# Baro_Touch.net
KiCad netlist of a schematic drawn in EAGLE
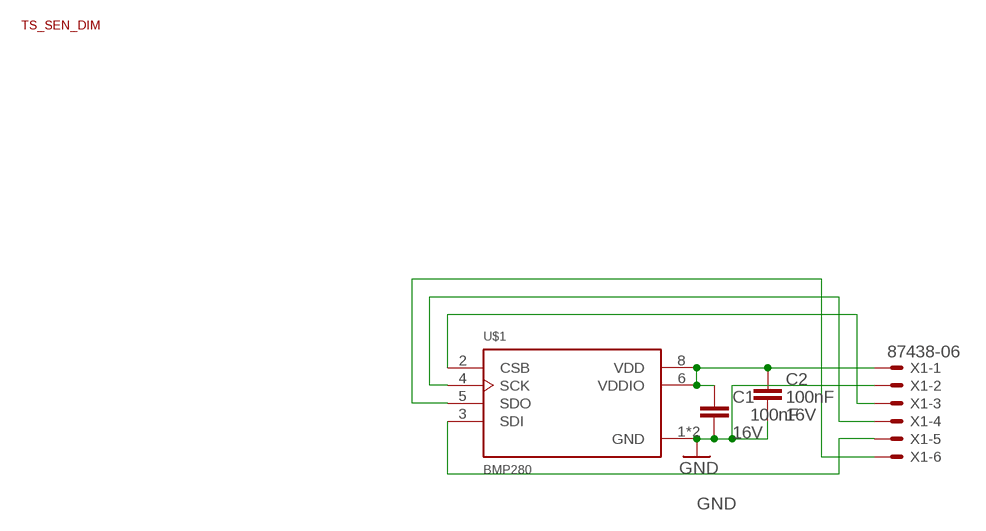
[diagram p0: schematic, sheet 1]

(export (version "E")
  (design (tool "Eeschema 10.0.6"))
  (components
    (comp (ref "C1")
      (value "GCM155R71C104JA55")
      (footprint "eagle-import:C0402")
      (fields
        (field (name "CAPACITANCE") "100nF")
        (field (name "TOLERANCE") "±5%")
        (field (name "VOLTAGE") "16V")
      )
      (libsource (lib "eagle-import") (part "GCM?R71551C104JA55"))
    )
    (comp (ref "C2")
      (value "GCM155R71C104JA55")
      (footprint "eagle-import:C0402")
      (fields
        (field (name "CAPACITANCE") "100nF")
        (field (name "TOLERANCE") "±5%")
        (field (name "VOLTAGE") "16V")
      )
      (libsource (lib "eagle-import") (part "GCM?R71551C104JA55"))
    )
    (comp (ref "DIMENSION1")
      (value "TS_SEN_DIM")
      (footprint "eagle-import:SEN_DIM")
      (libsource (lib "eagle-import") (part "TS_SEN_DIM"))
    )
    (comp (ref "U$1")
      (value "BMP280")
      (footprint "eagle-import:8-SMD")
      (libsource (lib "eagle-import") (part "BMP280"))
    )
    (comp (ref "X1")
      (value "87438-06")
      (footprint "eagle-import:87438-06")
      (fields (field (name "MF") "MOLEX") (field (name "MPN") "87438-0643"))
      (libsource (lib "eagle-import") (part "87438-06"))
    )
  )
  (nets
    (net (code "1") (name "GND") (class "Default")
      (node (ref "C1") (pin "2") (pinfunction "2_2") (pintype "passive"))
      (node (ref "C2") (pin "2") (pinfunction "2_2") (pintype "passive"))
      (node (ref "U$1") (pin "1") (pinfunction "GND_1") (pintype "power_in"))
      (node (ref "U$1") (pin "7") (pinfunction "GND_7") (pintype "power_in"))
      (node (ref "X1") (pin "2") (pinfunction "S_2") (pintype "passive"))
    )
    (net (code "2") (name "Net-(U$1-CSB)") (class "Default")
      (node (ref "U$1") (pin "2") (pinfunction "CSB_2") (pintype "input"))
      (node (ref "X1") (pin "3") (pinfunction "S_3") (pintype "passive"))
    )
    (net (code "3") (name "Net-(U$1-SCK)") (class "Default")
      (node (ref "U$1") (pin "4") (pinfunction "SCK_4") (pintype "input"))
      (node (ref "X1") (pin "4") (pinfunction "S_4") (pintype "passive"))
    )
    (net (code "4") (name "Net-(U$1-SDI)") (class "Default")
      (node (ref "U$1") (pin "3") (pinfunction "SDI_3") (pintype "bidirectional"))
      (node (ref "X1") (pin "5") (pinfunction "S_5") (pintype "passive"))
    )
    (net (code "5") (name "Net-(U$1-SDO)") (class "Default")
      (node (ref "U$1") (pin "5") (pinfunction "SDO_5") (pintype "output"))
      (node (ref "X1") (pin "6") (pinfunction "S_6") (pintype "passive"))
    )
    (net (code "6") (name "Net-(U$1-VDD)") (class "Default")
      (node (ref "C1") (pin "1") (pinfunction "1_1") (pintype "passive"))
      (node (ref "C2") (pin "1") (pinfunction "1_1") (pintype "passive"))
      (node (ref "U$1") (pin "6") (pinfunction "VDDIO_6") (pintype "power_in"))
      (node (ref "U$1") (pin "8") (pinfunction "VDD_8") (pintype "power_in"))
      (node (ref "X1") (pin "1") (pinfunction "S_1") (pintype "passive"))
    )
  )
)
